# Power.net
KiCad netlist of a schematic drawn in Altium Designer
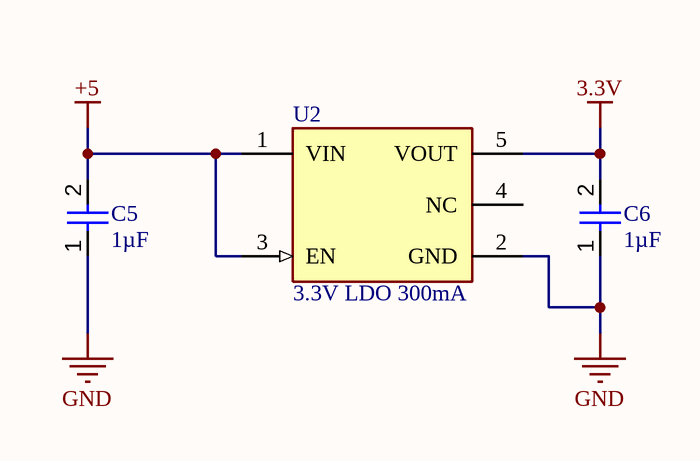
[diagram p0: Power.SchDoc]

(export (version "E")
  (design (tool "Eeschema 10.0.6"))
  (components
    (comp (ref "C5")
      (value "1µF")
      (footprint "CAP_0603")
      (description "Capacitor 1uF 10% 16V 0603")
      (fields (field (name "TOLERANCE") "10%") (field (name "Comment") "CAP 1uF"))
      (libsource (lib "Jack Bolte") (part "[0402] CAP 7.5pF"))
    )
    (comp (ref "C6")
      (value "1µF")
      (footprint "CAP_0603")
      (description "Capacitor 1uF 10% 16V 0603")
      (fields (field (name "TOLERANCE") "10%") (field (name "Comment") "CAP 1uF"))
      (libsource (lib "Jack Bolte") (part "[0402] CAP 7.5pF"))
    )
    (comp (ref "U2")
      (value "3.3V LDO 300mA")
      (footprint "FP-SOT23-5LD-PL-1-MFG")
      (description "Fixed Positive LDO Regulator, 3.3V, 0.38V Dropout, CMOS, PDSO5")
      (libsource (lib "Jack Bolte") (part "96048095611b4a9579e1e315950d302"))
    )
  )
  (nets
    (net (code "1") (name "+5") (class "Default")
      (node (ref "C5") (pin "2") (pinfunction "2_2") (pintype "passive"))
      (node (ref "U2") (pin "1") (pinfunction "VIN_1") (pintype "power_in"))
      (node (ref "U2") (pin "3") (pinfunction "EN_3") (pintype "input"))
    )
    (net (code "2") (name "3.3V") (class "Default")
      (node (ref "C6") (pin "2") (pinfunction "2_2") (pintype "passive"))
      (node (ref "U2") (pin "5") (pinfunction "VOUT_5") (pintype "power_in"))
    )
    (net (code "3") (name "GND") (class "Default")
      (node (ref "C5") (pin "1") (pinfunction "1_1") (pintype "passive"))
      (node (ref "C6") (pin "1") (pinfunction "1_1") (pintype "passive"))
      (node (ref "U2") (pin "2") (pinfunction "GND_2") (pintype "power_in"))
    )
    (net (code "4") (name "unconnected-(U2-NC-Pad4)") (class "Default")
      (node (ref "U2") (pin "4") (pinfunction "NC_4") (pintype "passive"))
    )
  )
)
